# main.net
KiCad netlist of a schematic drawn in Altium Designer
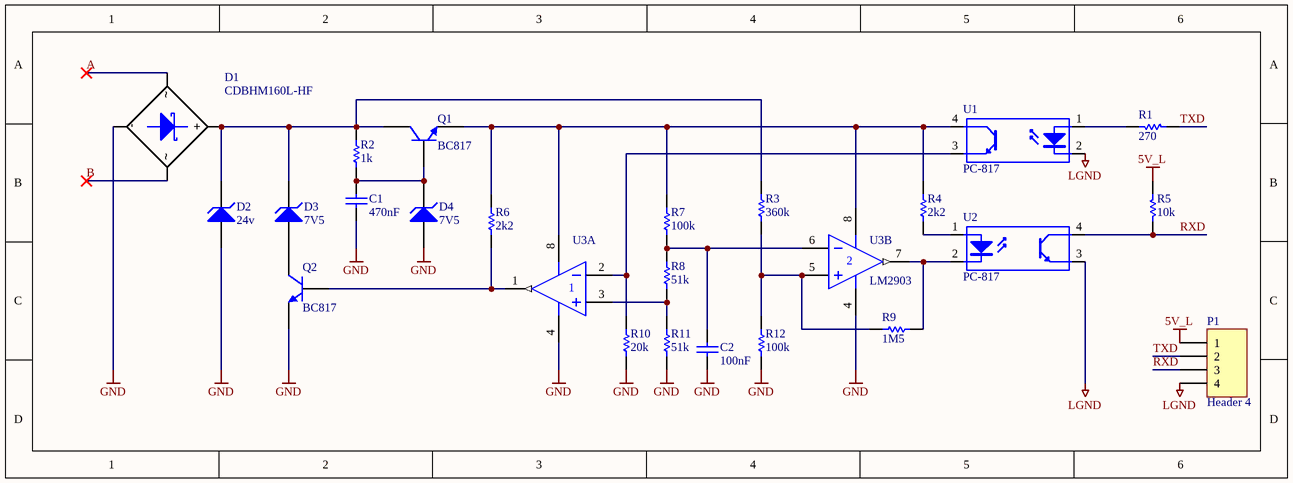
[diagram p0: main.SchDoc]

(export (version "E")
  (design (tool "Eeschema 10.0.6"))
  (components
    (comp (ref "C1")
      (value "470nF")
      (footprint "RC_0805_T0.8")
      (description "470nF 0805")
      (libsource (lib "Miscellaneous Devices") (part "Cap"))
    )
    (comp (ref "C2")
      (value "100nF")
      (footprint "RC_0805_T0.8")
      (description "100nF 0805")
      (libsource (lib "Miscellaneous Devices") (part "Cap"))
    )
    (comp (ref "D1")
      (value "CDBHM160L-HF")
      (footprint "RR_MBS")
      (libsource (lib "RozumLibrary") (part "CDBHM160L-HF"))
    )
    (comp (ref "D2")
      (value "24v")
      (footprint "RR_SOT-23")
      (description "Zener 24v SOT-23")
      (libsource (lib "Schlib1") (part "BZX84"))
    )
    (comp (ref "D3")
      (value "7V5")
      (footprint "RR_SOT-23")
      (description "Zener 7V5 SOT-23")
      (libsource (lib "Schlib1") (part "BZX84"))
    )
    (comp (ref "D4")
      (value "7V5")
      (footprint "RR_SOT-23")
      (description "Zener 7V5 SOT-23")
      (libsource (lib "Schlib1") (part "BZX84"))
    )
    (comp (ref "P1")
      (value "Header 4")
      (footprint "HDR1X4")
      (description "Header, 4-Pin")
      (libsource (lib "Miscellaneous Connectors") (part "Header 4"))
    )
    (comp (ref "Q1") (value "BC817") (footprint "SOT-23B_L") (libsource (lib "EDDLib") (part "NPN_SOT23")))
    (comp (ref "Q2") (value "BC817") (footprint "SOT-23B_L") (libsource (lib "EDDLib") (part "NPN_SOT23")))
    (comp (ref "R1")
      (value "270")
      (footprint "RR_0805")
      (description "270 0805")
      (libsource (lib "Miscellaneous Devices") (part "Res1"))
    )
    (comp (ref "R2")
      (value "1k")
      (footprint "RR_0805")
      (description "1k 0805")
      (libsource (lib "Miscellaneous Devices") (part "Res1"))
    )
    (comp (ref "R3")
      (value "360k")
      (footprint "RR_0805")
      (description "360k 0805")
      (libsource (lib "Miscellaneous Devices") (part "Res1"))
    )
    (comp (ref "R4")
      (value "2k2")
      (footprint "RR_0805")
      (description "2k2 0805")
      (libsource (lib "Miscellaneous Devices") (part "Res1"))
    )
    (comp (ref "R5")
      (value "10k")
      (footprint "RR_0805")
      (description "10k 0805")
      (libsource (lib "Miscellaneous Devices") (part "Res1"))
    )
    (comp (ref "R6")
      (value "2k2")
      (footprint "RR_0805")
      (description "2k2 0805")
      (libsource (lib "Miscellaneous Devices") (part "Res1"))
    )
    (comp (ref "R7")
      (value "100k")
      (footprint "RR_0805")
      (description "100k 0805")
      (libsource (lib "Miscellaneous Devices") (part "Res1"))
    )
    (comp (ref "R8")
      (value "51k")
      (footprint "RR_0805")
      (description "51k 0805")
      (libsource (lib "Miscellaneous Devices") (part "Res1"))
    )
    (comp (ref "R9")
      (value "1M5")
      (footprint "RR_0805")
      (description "1M5 0805")
      (libsource (lib "Miscellaneous Devices") (part "Res1"))
    )
    (comp (ref "R10")
      (value "20k")
      (footprint "RR_0805")
      (description "20k 0805")
      (libsource (lib "Miscellaneous Devices") (part "Res1"))
    )
    (comp (ref "R11")
      (value "51k")
      (footprint "RR_0805")
      (description "51k 0805")
      (libsource (lib "Miscellaneous Devices") (part "Res1"))
    )
    (comp (ref "R12")
      (value "100k")
      (footprint "RR_0805")
      (description "100k 0805")
      (libsource (lib "Miscellaneous Devices") (part "Res1"))
    )
    (comp (ref "U1")
      (value "PC-817")
      (footprint "RR_DIP_SM4")
      (libsource (lib "Miscellaneous Devices") (part "Optoisolator1"))
    )
    (comp (ref "U2")
      (value "PC-817")
      (footprint "RR_DIP_SM4")
      (libsource (lib "Miscellaneous Devices") (part "Optoisolator1"))
    )
    (comp (ref "U3")
      (value "LM2903")
      (footprint "RR_SO-8")
      (libsource (lib "RozumLibrary") (part "LM393ADR"))
    )
  )
  (nets
    (net (code "1") (name "/A") (class "Default")
      (node (ref "D1") (pin "3") (pinfunction "K_3") (pintype "passive+no_connect"))
    )
    (net (code "2") (name "/B") (class "Default")
      (node (ref "D1") (pin "4") (pinfunction "K_4") (pintype "passive+no_connect"))
    )
    (net (code "3") (name "/RXD") (class "Default")
      (node (ref "P1") (pin "3") (pinfunction "3_3") (pintype "passive"))
      (node (ref "R5") (pin "2") (pinfunction "2_2") (pintype "passive"))
      (node (ref "U2") (pin "4") (pinfunction "C_4") (pintype "passive"))
    )
    (net (code "4") (name "/TXD") (class "Default")
      (node (ref "P1") (pin "2") (pinfunction "2_2") (pintype "passive"))
      (node (ref "R1") (pin "1") (pinfunction "1_1") (pintype "passive"))
    )
    (net (code "5") (name "5V_L") (class "Default")
      (node (ref "P1") (pin "1") (pinfunction "1_1") (pintype "passive"))
      (node (ref "R5") (pin "1") (pinfunction "1_1") (pintype "passive"))
    )
    (net (code "6") (name "GND") (class "Default")
      (node (ref "C1") (pin "1") (pinfunction "1_1") (pintype "passive"))
      (node (ref "C2") (pin "1") (pinfunction "1_1") (pintype "passive"))
      (node (ref "D1") (pin "2") (pinfunction "A_2") (pintype "passive"))
      (node (ref "D2") (pin "1") (pinfunction "A_1") (pintype "passive"))
      (node (ref "D4") (pin "1") (pinfunction "A_1") (pintype "passive"))
      (node (ref "Q2") (pin "2") (pinfunction "E_2") (pintype "passive"))
      (node (ref "R10") (pin "2") (pinfunction "2_2") (pintype "passive"))
      (node (ref "R11") (pin "2") (pinfunction "2_2") (pintype "passive"))
      (node (ref "R12") (pin "2") (pinfunction "2_2") (pintype "passive"))
      (node (ref "U3") (pin "4") (pinfunction "V-_4") (pintype "power_in"))
    )
    (net (code "7") (name "LGND") (class "Default")
      (node (ref "P1") (pin "4") (pinfunction "4_4") (pintype "passive"))
      (node (ref "U1") (pin "2") (pinfunction "K_2") (pintype "passive"))
      (node (ref "U2") (pin "3") (pinfunction "E_3") (pintype "passive"))
    )
    (net (code "8") (name "Net-(Q1-B)") (class "Default")
      (node (ref "C1") (pin "2") (pinfunction "2_2") (pintype "passive"))
      (node (ref "D4") (pin "3") (pinfunction "A_3") (pintype "passive"))
      (node (ref "Q1") (pin "1") (pinfunction "B_1") (pintype "passive"))
      (node (ref "R2") (pin "1") (pinfunction "1_1") (pintype "passive"))
    )
    (net (code "9") (name "Net-(Q1-C)") (class "Default")
      (node (ref "D1") (pin "1") (pinfunction "K_1") (pintype "passive"))
      (node (ref "D2") (pin "3") (pinfunction "A_3") (pintype "passive"))
      (node (ref "D3") (pin "3") (pinfunction "A_3") (pintype "passive"))
      (node (ref "Q1") (pin "3") (pinfunction "C_3") (pintype "passive"))
      (node (ref "R2") (pin "2") (pinfunction "2_2") (pintype "passive"))
      (node (ref "R3") (pin "2") (pinfunction "2_2") (pintype "passive"))
    )
    (net (code "10") (name "Net-(Q1-E)") (class "Default")
      (node (ref "Q1") (pin "2") (pinfunction "E_2") (pintype "passive"))
      (node (ref "R4") (pin "1") (pinfunction "1_1") (pintype "passive"))
      (node (ref "R6") (pin "1") (pinfunction "1_1") (pintype "passive"))
      (node (ref "R7") (pin "1") (pinfunction "1_1") (pintype "passive"))
      (node (ref "U1") (pin "4") (pinfunction "C_4") (pintype "passive"))
      (node (ref "U3") (pin "8") (pinfunction "V+_8") (pintype "power_in"))
    )
    (net (code "11") (name "Net-(Q2-B)") (class "Default")
      (node (ref "Q2") (pin "1") (pinfunction "B_1") (pintype "passive"))
      (node (ref "R6") (pin "2") (pinfunction "2_2") (pintype "passive"))
      (node (ref "U3") (pin "1") (pinfunction "OUT_1") (pintype "output"))
    )
    (net (code "12") (name "Net-(Q2-C)") (class "Default")
      (node (ref "D3") (pin "1") (pinfunction "A_1") (pintype "passive"))
      (node (ref "Q2") (pin "3") (pinfunction "C_3") (pintype "passive"))
    )
    (net (code "13") (name "Net-(U1-A)") (class "Default")
      (node (ref "R1") (pin "2") (pinfunction "2_2") (pintype "passive"))
      (node (ref "U1") (pin "1") (pinfunction "A_1") (pintype "passive"))
    )
    (net (code "14") (name "Net-(U1-E)") (class "Default")
      (node (ref "R10") (pin "1") (pinfunction "1_1") (pintype "passive"))
      (node (ref "U1") (pin "3") (pinfunction "E_3") (pintype "passive"))
      (node (ref "U3") (pin "2") (pinfunction "IN-_2") (pintype "passive"))
    )
    (net (code "15") (name "Net-(U2-A)") (class "Default")
      (node (ref "R4") (pin "2") (pinfunction "2_2") (pintype "passive"))
      (node (ref "U2") (pin "1") (pinfunction "A_1") (pintype "passive"))
    )
    (net (code "16") (name "Net-(U2-K)") (class "Default")
      (node (ref "R9") (pin "2") (pinfunction "2_2") (pintype "passive"))
      (node (ref "U2") (pin "2") (pinfunction "K_2") (pintype "passive"))
      (node (ref "U3") (pin "7") (pinfunction "OUT_7") (pintype "output"))
    )
    (net (code "17") (name "Net-(U3A-IN+)") (class "Default")
      (node (ref "R11") (pin "1") (pinfunction "1_1") (pintype "passive"))
      (node (ref "R8") (pin "2") (pinfunction "2_2") (pintype "passive"))
      (node (ref "U3") (pin "3") (pinfunction "IN+_3") (pintype "passive"))
    )
    (net (code "18") (name "Net-(U3B-IN+)") (class "Default")
      (node (ref "R12") (pin "1") (pinfunction "1_1") (pintype "passive"))
      (node (ref "R3") (pin "1") (pinfunction "1_1") (pintype "passive"))
      (node (ref "R9") (pin "1") (pinfunction "1_1") (pintype "passive"))
      (node (ref "U3") (pin "5") (pinfunction "IN+_5") (pintype "input"))
    )
    (net (code "19") (name "Net-(U3B-IN-)") (class "Default")
      (node (ref "C2") (pin "2") (pinfunction "2_2") (pintype "passive"))
      (node (ref "R7") (pin "2") (pinfunction "2_2") (pintype "passive"))
      (node (ref "R8") (pin "1") (pinfunction "1_1") (pintype "passive"))
      (node (ref "U3") (pin "6") (pinfunction "IN-_6") (pintype "input"))
    )
  )
)
